# LCD.net
KiCad netlist of a schematic drawn in Altium Designer
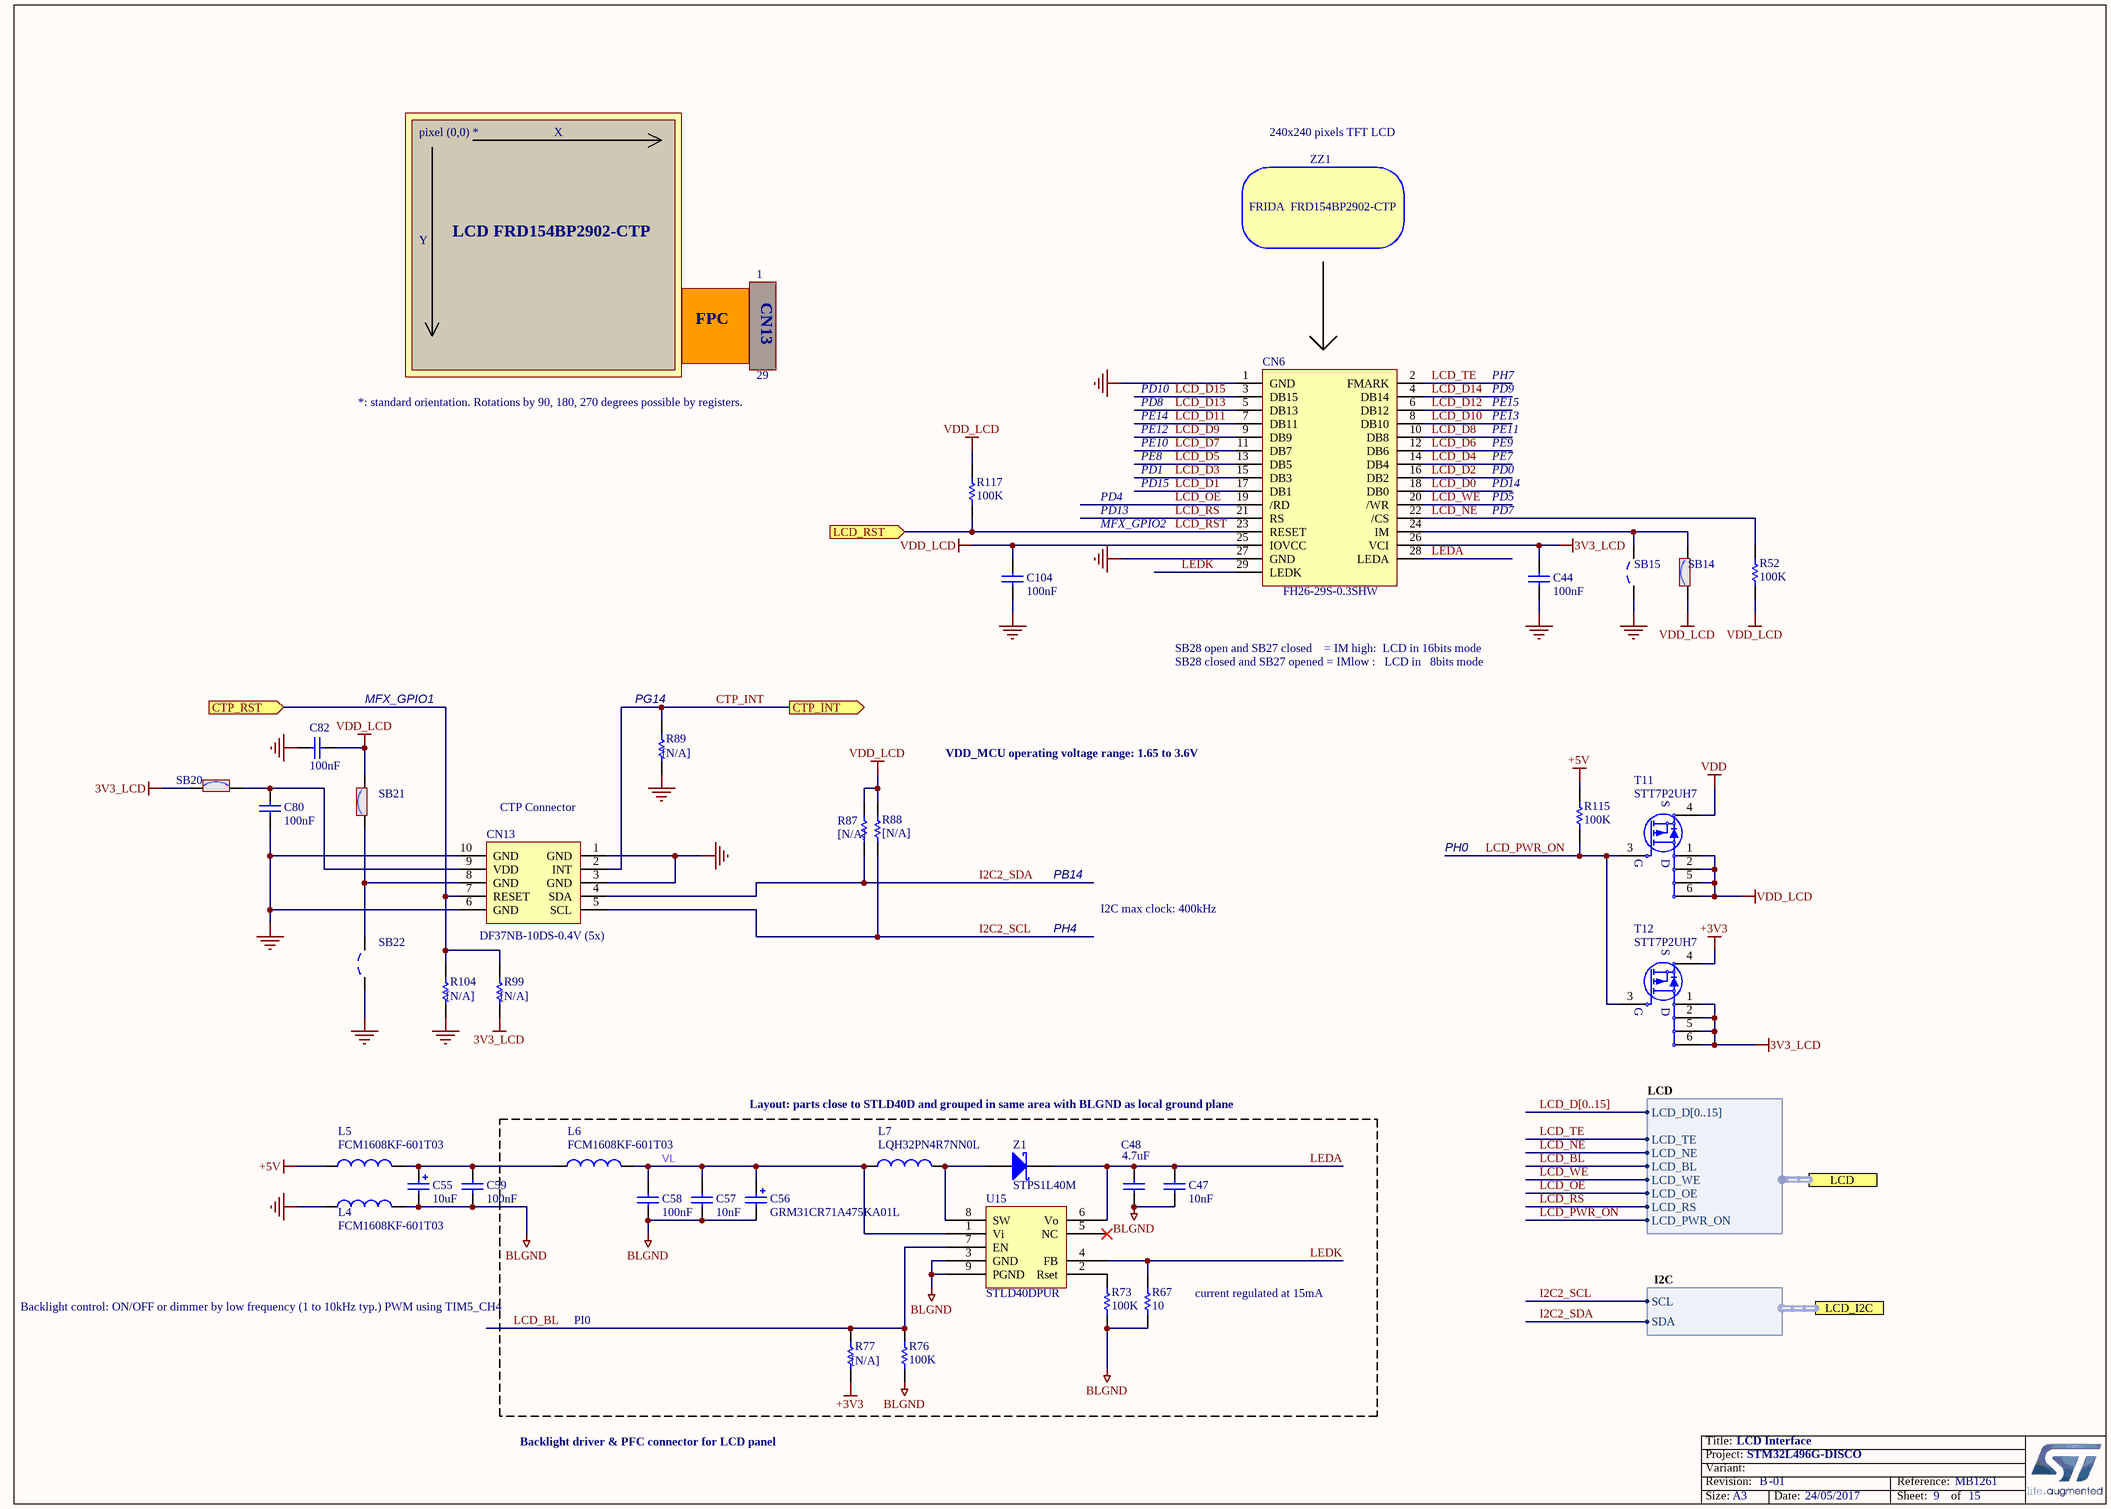
[diagram p0: LCD.SchDoc]

(export (version "E")
  (design (tool "Eeschema 10.0.6"))
  (components
    (comp (ref "C44")
      (value "100nF")
      (footprint "0603C")
      (description "Capacitor,100nF,10%,16V,X7R,0603,YAGEO")
      (fields (field (name "Comment") "CC0603KRX7R7BB104") (field (name "PUBLISHER") "Altium Limited"))
      (libsource (lib "Miscellaneous Devices") (part "Cap"))
    )
    (comp (ref "C47")
      (value "10nF")
      (footprint "0603C")
      (description "Capacitor,10nF,0603,50V,10%,X7R,YAGEO;")
      (fields (field (name "Comment") "CC0603KRX7R9BB103") (field (name "PUBLISHER") "Altium Limited"))
      (libsource (lib "Miscellaneous Devices") (part "Cap"))
    )
    (comp (ref "C48")
      (value "4.7uF")
      (footprint "1206C")
      (description "Capacitor,4.7uF,50V,X7R,10%,1206")
      (fields (field (name "Comment") "CC1206KKX7R9BB475") (field (name "PUBLISHER") "Altium Limited"))
      (libsource (lib "Miscellaneous Devices") (part "CAP"))
    )
    (comp (ref "C55")
      (value "10uF")
      (footprint "TAN-A")
      (description "TAN Capacitor,10uF,10%,16V,A Type,AVX")
      (fields (field (name "Comment") "TAJA106K016R") (field (name "PUBLISHER") "Altium Limited"))
      (libsource (lib "Miscellaneous Devices") (part "Cap Pol1"))
    )
    (comp (ref "C56")
      (value "GRM31CR71A475KA01L")
      (footprint "1206C")
      (description "Capacitor,4.7uF,±10%,X7R,10V,1206,GRM31CR71A475KA01L")
      (fields (field (name "PUBLISHER") "Altium Limited"))
      (libsource (lib "Miscellaneous Devices") (part "Cap Pol1"))
    )
    (comp (ref "C57")
      (value "10nF")
      (footprint "0603C")
      (description "Capacitor,10nF,0603,50V,10%,X7R,YAGEO;")
      (fields (field (name "Comment") "CC0603KRX7R9BB103") (field (name "PUBLISHER") "Altium Limited"))
      (libsource (lib "Miscellaneous Devices") (part "Cap"))
    )
    (comp (ref "C58")
      (value "100nF")
      (footprint "0603C")
      (description "Capacitor,100nF,10%,16V,X7R,0603,YAGEO")
      (fields (field (name "Comment") "CC0603KRX7R7BB104") (field (name "PUBLISHER") "Altium Limited"))
      (libsource (lib "Miscellaneous Devices") (part "Cap"))
    )
    (comp (ref "C59")
      (value "100nF")
      (footprint "0603C")
      (description "Capacitor,100nF,10%,16V,X7R,0603,YAGEO")
      (fields (field (name "Comment") "CC0603KRX7R7BB104") (field (name "PUBLISHER") "Altium Limited"))
      (libsource (lib "Miscellaneous Devices") (part "Cap"))
    )
    (comp (ref "C80")
      (value "100nF")
      (footprint "0603C")
      (description "Capacitor,100nF,10%,16V,X7R,0603,YAGEO")
      (fields (field (name "Comment") "CC0603KRX7R7BB104") (field (name "PUBLISHER") "Altium Limited"))
      (libsource (lib "Miscellaneous Devices") (part "Cap"))
    )
    (comp (ref "C82")
      (value "100nF")
      (footprint "0603C")
      (description "Capacitor,100nF,10%,16V,X7R,0603,YAGEO")
      (fields (field (name "Comment") "CC0603KRX7R7BB104") (field (name "PUBLISHER") "Altium Limited"))
      (libsource (lib "Miscellaneous Devices") (part "Cap"))
    )
    (comp (ref "C104")
      (value "100nF")
      (footprint "0603C")
      (description "Capacitor,100nF,10%,16V,X7R,0603,YAGEO")
      (fields (field (name "Comment") "CC0603KRX7R7BB104") (field (name "PUBLISHER") "Altium Limited"))
      (libsource (lib "Miscellaneous Devices") (part "Cap"))
    )
    (comp (ref "CN6")
      (value "FH26-29S-0.3SHW")
      (footprint "FH26-29S-0R3SHW")
      (description "29pins FPC connector")
      (libsource (lib "MB1209_3") (part "FH26-29S-0.3SHW"))
    )
    (comp (ref "CN13")
      (value "DF37NB-10DS-0.4V (5x)")
      (footprint "DF37NB-10DS-0R4V")
      (description "Header, 5-Pin, Dual row")
      (fields (field (name "PUBLISHER") "Altium Limited"))
      (libsource (lib "MB1209") (part "Header 5X2A"))
    )
    (comp (ref "L4")
      (value "FCM1608KF-601T03")
      (footprint "0603L")
      (description "100uH Bead")
      (fields (field (name "PUBLISHER") "Altium Limited"))
      (libsource (lib "Miscellaneous Devices") (part "Inductor"))
    )
    (comp (ref "L5")
      (value "FCM1608KF-601T03")
      (footprint "0603L")
      (description "100uH Bead")
      (fields (field (name "PUBLISHER") "Altium Limited"))
      (libsource (lib "Miscellaneous Devices") (part "Inductor"))
    )
    (comp (ref "L6")
      (value "FCM1608KF-601T03")
      (footprint "0603L")
      (description "100uH Bead")
      (fields (field (name "PUBLISHER") "Altium Limited"))
      (libsource (lib "Miscellaneous Devices") (part "Inductor"))
    )
    (comp (ref "L7")
      (value "LQH32PN4R7NN0L")
      (footprint "1210L")
      (description "IND,4.7uH,1A,1210,LQH32PN4R7NN0L")
      (fields (field (name "PUBLISHER") "Altium Limited"))
      (libsource (lib "Miscellaneous Devices") (part "Inductor"))
    )
    (comp (ref "R52")
      (value "100K")
      (footprint "0603R")
      (description "Resistor,100K,0603,1%,YAGEO")
      (fields (field (name "Comment") "RC0603FR-07100KL") (field (name "PUBLISHER") "Altium Limited"))
      (libsource (lib "Miscellaneous Devices") (part "res1"))
    )
    (comp (ref "R67")
      (value "10")
      (footprint "0603R")
      (description "Resistor,10R,0603,1%,YAGEO")
      (fields (field (name "Comment") "RC0603FR-0710RL") (field (name "PUBLISHER") "Altium Limited"))
      (libsource (lib "Miscellaneous Devices") (part "res1"))
    )
    (comp (ref "R73")
      (value "100K")
      (footprint "0603R")
      (description "Resistor,100K,0603,1%,YAGEO")
      (fields (field (name "Comment") "RC0603FR-07100KL") (field (name "PUBLISHER") "Altium Limited"))
      (libsource (lib "Miscellaneous Devices") (part "res1"))
    )
    (comp (ref "R76")
      (value "100K")
      (footprint "0603R")
      (description "Resistor,100K,0603,1%,YAGEO")
      (fields (field (name "Comment") "RC0603FR-07100KL") (field (name "PUBLISHER") "Altium Limited"))
      (libsource (lib "Miscellaneous Devices") (part "res1"))
    )
    (comp (ref "R77")
      (value "[N/A]")
      (footprint "0603R")
      (description "Resistor,100K,0603,1%,YAGEO")
      (fields (field (name "PUBLISHER") "Altium Limited"))
      (libsource (lib "Miscellaneous Devices") (part "res1"))
    )
    (comp (ref "R87")
      (value "[N/A]")
      (footprint "0603R")
      (description "Resistor,1.5K,0603,1%,YAGEO")
      (fields (field (name "PUBLISHER") "Altium Limited"))
      (libsource (lib "Miscellaneous Devices") (part "res1"))
    )
    (comp (ref "R88")
      (value "[N/A]")
      (footprint "0603R")
      (description "Resistor,1.5K,0603,1%,YAGEO")
      (fields (field (name "PUBLISHER") "Altium Limited"))
      (libsource (lib "Miscellaneous Devices") (part "res1"))
    )
    (comp (ref "R89")
      (value "[N/A]")
      (footprint "0603R")
      (description "Resistor,100K,0603,1%,YAGEO")
      (fields (field (name "PUBLISHER") "Altium Limited"))
      (libsource (lib "Miscellaneous Devices") (part "res1"))
    )
    (comp (ref "R99")
      (value "[N/A]")
      (footprint "0603R")
      (description "Resistor,100K,0603,1%,YAGEO")
      (fields (field (name "PUBLISHER") "Altium Limited"))
      (libsource (lib "Miscellaneous Devices") (part "res1"))
    )
    (comp (ref "R104")
      (value "[N/A]")
      (footprint "0603R")
      (description "Resistor,100K,0603,1%,YAGEO")
      (fields (field (name "PUBLISHER") "Altium Limited"))
      (libsource (lib "Miscellaneous Devices") (part "res1"))
    )
    (comp (ref "R115")
      (value "100K")
      (footprint "0603R")
      (description "Resistor,100K,0603,1%,YAGEO")
      (fields (field (name "Comment") "RC0603FR-07100KL") (field (name "PUBLISHER") "Altium Limited"))
      (libsource (lib "Miscellaneous Devices") (part "res1"))
    )
    (comp (ref "R117")
      (value "100K")
      (footprint "0603R")
      (description "Resistor,100K,0603,1%,YAGEO")
      (fields (field (name "Comment") "RC0603FR-07100KL") (field (name "PUBLISHER") "Altium Limited"))
      (libsource (lib "Miscellaneous Devices") (part "res1"))
    )
    (comp (ref "SB14")
      (value "Solder Bridge ON")
      (footprint "SB_0603")
      (libsource (lib "MCD_TOOLS") (part "SB_ON"))
    )
    (comp (ref "SB15")
      (value "Solder Bridge OFF")
      (footprint "SB_0603")
      (libsource (lib "MCD_TOOLS") (part "SB_OFF"))
    )
    (comp (ref "SB20") (value "Solder Bridge ON") (footprint "SB_0603") (libsource (lib "") (part "SB_ON_1")))
    (comp (ref "SB21")
      (value "Solder Bridge ON")
      (footprint "SB_0603")
      (libsource (lib "MCD_TOOLS") (part "SB_ON"))
    )
    (comp (ref "SB22")
      (value "Solder Bridge OFF")
      (footprint "SB_0603")
      (libsource (lib "MCD_TOOLS") (part "SB_OFF"))
    )
    (comp (ref "T11")
      (value "STT7P2UH7")
      (footprint "SOT23-6L")
      (description "STripFET VII DeepGATE Power MOSFET, P-CHANNEL 20 V, 0.0146, 7 A - SOT23-6L")
      (libsource (lib "MCD_TOOLS") (part "STT7P2UH7"))
    )
    (comp (ref "T12")
      (value "STT7P2UH7")
      (footprint "SOT23-6L")
      (description "STripFET VII DeepGATE Power MOSFET, P-CHANNEL 20 V, 0.0146, 7 A - SOT23-6L")
      (libsource (lib "MCD_TOOLS") (part "STT7P2UH7"))
    )
    (comp (ref "U15")
      (value "STLD40DPUR")
      (footprint "SON8_0R65_3X3")
      (libsource (lib "3.2LCD_daughterboard") (part "STLD40DPMR"))
    )
    (comp (ref "Z1")
      (value "STPS1L40M")
      (footprint "DO-216AA")
      (description "Schottky Diode")
      (fields (field (name "PUBLISHER") "Altium Limited"))
      (libsource (lib "Miscellaneous Devices") (part "D Schottky"))
    )
    (comp (ref "ZZ1")
      (value "FRIDA  FRD154BP2902-CTP")
      (footprint "LCD_FRD154BP2902-CTP")
      (libsource (lib "Almos") (part "BoM_Item"))
    )
  )
  (nets
    (net (code "3") (name "+3V3") (class "Default")
      (node (ref "R77") (pin "2") (pinfunction "2_2") (pintype "passive"))
      (node (ref "T12") (pin "4") (pinfunction "S_4") (pintype "passive"))
    )
    (net (code "4") (name "+5V") (class "Default")
      (node (ref "L5") (pin "1") (pinfunction "1_1") (pintype "passive"))
      (node (ref "R115") (pin "1") (pinfunction "1_1") (pintype "passive"))
    )
    (net (code "5") (name "/CTP_INT") (class "Default")
      (node (ref "CN13") (pin "2") (pinfunction "INT_2") (pintype "passive"))
      (node (ref "R89") (pin "1") (pinfunction "1_1") (pintype "passive"))
    )
    (net (code "6") (name "/CTP_RST") (class "Default")
      (node (ref "CN13") (pin "7") (pinfunction "RESET_7") (pintype "passive"))
      (node (ref "R104") (pin "1") (pinfunction "1_1") (pintype "passive"))
      (node (ref "R99") (pin "1") (pinfunction "1_1") (pintype "passive"))
    )
    (net (code "7") (name "/I2C2_SCL") (class "Default")
      (node (ref "CN13") (pin "5") (pinfunction "SCL_5") (pintype "passive"))
      (node (ref "R88") (pin "2") (pinfunction "2_2") (pintype "passive"))
    )
    (net (code "8") (name "/I2C2_SDA") (class "Default")
      (node (ref "CN13") (pin "4") (pinfunction "SDA_4") (pintype "passive"))
      (node (ref "R87") (pin "1") (pinfunction "1_1") (pintype "passive"))
    )
    (net (code "9") (name "/LCD_BL") (class "Default")
      (node (ref "R76") (pin "1") (pinfunction "1_1") (pintype "passive"))
      (node (ref "R77") (pin "1") (pinfunction "1_1") (pintype "passive"))
      (node (ref "U15") (pin "7") (pinfunction "EN_7") (pintype "passive"))
    )
    (net (code "10") (name "/LCD_D0") (class "Default")
      (node (ref "CN6") (pin "18") (pinfunction "DB0_18") (pintype "passive"))
    )
    (net (code "11") (name "/LCD_D1") (class "Default")
      (node (ref "CN6") (pin "17") (pinfunction "DB1_17") (pintype "passive"))
    )
    (net (code "12") (name "/LCD_D2") (class "Default")
      (node (ref "CN6") (pin "16") (pinfunction "DB2_16") (pintype "passive"))
    )
    (net (code "13") (name "/LCD_D3") (class "Default")
      (node (ref "CN6") (pin "15") (pinfunction "DB3_15") (pintype "passive"))
    )
    (net (code "14") (name "/LCD_D4") (class "Default")
      (node (ref "CN6") (pin "14") (pinfunction "DB4_14") (pintype "passive"))
    )
    (net (code "15") (name "/LCD_D5") (class "Default")
      (node (ref "CN6") (pin "13") (pinfunction "DB5_13") (pintype "passive"))
    )
    (net (code "16") (name "/LCD_D6") (class "Default")
      (node (ref "CN6") (pin "12") (pinfunction "DB6_12") (pintype "passive"))
    )
    (net (code "17") (name "/LCD_D7") (class "Default")
      (node (ref "CN6") (pin "11") (pinfunction "DB7_11") (pintype "passive"))
    )
    (net (code "18") (name "/LCD_D8") (class "Default")
      (node (ref "CN6") (pin "10") (pinfunction "DB8_10") (pintype "passive"))
    )
    (net (code "19") (name "/LCD_D9") (class "Default")
      (node (ref "CN6") (pin "9") (pinfunction "DB9_9") (pintype "passive"))
    )
    (net (code "20") (name "/LCD_D10") (class "Default")
      (node (ref "CN6") (pin "8") (pinfunction "DB10_8") (pintype "passive"))
    )
    (net (code "21") (name "/LCD_D11") (class "Default")
      (node (ref "CN6") (pin "7") (pinfunction "DB11_7") (pintype "passive"))
    )
    (net (code "22") (name "/LCD_D12") (class "Default")
      (node (ref "CN6") (pin "6") (pinfunction "DB12_6") (pintype "passive"))
    )
    (net (code "23") (name "/LCD_D13") (class "Default")
      (node (ref "CN6") (pin "5") (pinfunction "DB13_5") (pintype "passive"))
    )
    (net (code "24") (name "/LCD_D14") (class "Default")
      (node (ref "CN6") (pin "4") (pinfunction "DB14_4") (pintype "passive"))
    )
    (net (code "25") (name "/LCD_D15") (class "Default")
      (node (ref "CN6") (pin "3") (pinfunction "DB15_3") (pintype "passive"))
    )
    (net (code "27") (name "/LCD_NE") (class "Default")
      (node (ref "CN6") (pin "22") (pinfunction "/CS_22") (pintype "passive"))
      (node (ref "R52") (pin "1") (pinfunction "1_1") (pintype "passive"))
    )
    (net (code "28") (name "/LCD_OE") (class "Default")
      (node (ref "CN6") (pin "19") (pinfunction "/RD_19") (pintype "passive"))
    )
    (net (code "29") (name "/LCD_PWR_ON") (class "Default")
      (node (ref "R115") (pin "2") (pinfunction "2_2") (pintype "passive"))
      (node (ref "T11") (pin "3") (pinfunction "G_3") (pintype "passive"))
      (node (ref "T12") (pin "3") (pinfunction "G_3") (pintype "passive"))
    )
    (net (code "30") (name "/LCD_RS") (class "Default")
      (node (ref "CN6") (pin "21") (pinfunction "RS_21") (pintype "passive"))
    )
    (net (code "31") (name "/LCD_RST") (class "Default")
      (node (ref "CN6") (pin "23") (pinfunction "RESET_23") (pintype "passive"))
      (node (ref "R117") (pin "2") (pinfunction "2_2") (pintype "passive"))
    )
    (net (code "32") (name "/LCD_TE") (class "Default")
      (node (ref "CN6") (pin "2") (pinfunction "FMARK_2") (pintype "passive"))
    )
    (net (code "33") (name "/LCD_WE") (class "Default")
      (node (ref "CN6") (pin "20") (pinfunction "/WR_20") (pintype "passive"))
    )
    (net (code "34") (name "/LEDA") (class "Default")
      (node (ref "C47") (pin "1") (pinfunction "1_1") (pintype "passive"))
      (node (ref "C48") (pin "1") (pinfunction "1_1") (pintype "passive"))
      (node (ref "CN6") (pin "28") (pinfunction "LEDA_28") (pintype "passive"))
      (node (ref "U15") (pin "6") (pinfunction "Vo_6") (pintype "passive"))
      (node (ref "Z1") (pin "2") (pinfunction "K_2") (pintype "passive"))
    )
    (net (code "35") (name "/LEDK") (class "Default")
      (node (ref "CN6") (pin "29") (pinfunction "LEDK_29") (pintype "passive"))
      (node (ref "R67") (pin "1") (pinfunction "1_1") (pintype "passive"))
      (node (ref "U15") (pin "4") (pinfunction "FB_4") (pintype "passive"))
    )
    (net (code "36") (name "/VL") (class "Default")
      (node (ref "C56") (pin "1") (pinfunction "1_1") (pintype "passive"))
      (node (ref "C57") (pin "1") (pinfunction "1_1") (pintype "passive"))
      (node (ref "C58") (pin "1") (pinfunction "1_1") (pintype "passive"))
      (node (ref "L6") (pin "2") (pinfunction "2_2") (pintype "passive"))
      (node (ref "L7") (pin "1") (pinfunction "1_1") (pintype "passive"))
      (node (ref "U15") (pin "1") (pinfunction "Vi_1") (pintype "passive"))
    )
    (net (code "39") (name "3V3_LCD") (class "Default")
      (node (ref "C44") (pin "1") (pinfunction "1_1") (pintype "passive"))
      (node (ref "CN6") (pin "26") (pinfunction "VCI_26") (pintype "passive"))
      (node (ref "R99") (pin "2") (pinfunction "2_2") (pintype "passive"))
      (node (ref "SB20") (pin "1") (pinfunction "1_1") (pintype "passive"))
      (node (ref "T12") (pin "1") (pinfunction "S_1") (pintype "passive"))
      (node (ref "T12") (pin "2") (pinfunction "S_2") (pintype "passive"))
      (node (ref "T12") (pin "5") (pinfunction "D_5") (pintype "passive"))
      (node (ref "T12") (pin "6") (pinfunction "D_6") (pintype "passive"))
    )
    (net (code "40") (name "BLGND") (class "Default")
      (node (ref "C47") (pin "2") (pinfunction "2_2") (pintype "passive"))
      (node (ref "C48") (pin "2") (pinfunction "2_2") (pintype "passive"))
      (node (ref "C55") (pin "2") (pinfunction "2_2") (pintype "passive"))
      (node (ref "C56") (pin "2") (pinfunction "2_2") (pintype "passive"))
      (node (ref "C57") (pin "2") (pinfunction "2_2") (pintype "passive"))
      (node (ref "C58") (pin "2") (pinfunction "2_2") (pintype "passive"))
      (node (ref "C59") (pin "2") (pinfunction "2_2") (pintype "passive"))
      (node (ref "L4") (pin "2") (pinfunction "2_2") (pintype "passive"))
      (node (ref "R67") (pin "2") (pinfunction "2_2") (pintype "passive"))
      (node (ref "R73") (pin "2") (pinfunction "2_2") (pintype "passive"))
      (node (ref "R76") (pin "2") (pinfunction "2_2") (pintype "passive"))
      (node (ref "U15") (pin "3") (pinfunction "GND_3") (pintype "passive"))
      (node (ref "U15") (pin "9") (pinfunction "PGND_9") (pintype "passive"))
    )
    (net (code "41") (name "GND") (class "Default")
      (node (ref "C104") (pin "2") (pinfunction "2_2") (pintype "passive"))
      (node (ref "C44") (pin "2") (pinfunction "2_2") (pintype "passive"))
      (node (ref "C80") (pin "2") (pinfunction "2_2") (pintype "passive"))
      (node (ref "C82") (pin "2") (pinfunction "2_2") (pintype "passive"))
      (node (ref "CN13") (pin "1") (pinfunction "GND_1") (pintype "passive"))
      (node (ref "CN13") (pin "10") (pinfunction "GND_10") (pintype "passive"))
      (node (ref "CN13") (pin "3") (pinfunction "GND_3") (pintype "passive"))
      (node (ref "CN13") (pin "6") (pinfunction "GND_6") (pintype "passive"))
      (node (ref "CN6") (pin "1") (pinfunction "GND_1") (pintype "passive"))
      (node (ref "CN6") (pin "27") (pinfunction "GND_27") (pintype "passive"))
      (node (ref "L4") (pin "1") (pinfunction "1_1") (pintype "passive"))
      (node (ref "R104") (pin "2") (pinfunction "2_2") (pintype "passive"))
      (node (ref "R89") (pin "2") (pinfunction "2_2") (pintype "passive"))
      (node (ref "SB15") (pin "1") (pinfunction "1_1") (pintype "passive"))
      (node (ref "SB22") (pin "1") (pinfunction "1_1") (pintype "passive"))
    )
    (net (code "42") (name "Net-(C55-Pad1)") (class "Default")
      (node (ref "C55") (pin "1") (pinfunction "1_1") (pintype "passive"))
      (node (ref "C59") (pin "1") (pinfunction "1_1") (pintype "passive"))
      (node (ref "L5") (pin "2") (pinfunction "2_2") (pintype "passive"))
      (node (ref "L6") (pin "1") (pinfunction "1_1") (pintype "passive"))
    )
    (net (code "43") (name "Net-(CN6-IM)") (class "Default")
      (node (ref "CN6") (pin "24") (pinfunction "IM_24") (pintype "passive"))
      (node (ref "SB14") (pin "2") (pinfunction "2_2") (pintype "passive"))
      (node (ref "SB15") (pin "2") (pinfunction "2_2") (pintype "passive"))
    )
    (net (code "44") (name "Net-(CN13-GND-Pad8)") (class "Default")
      (node (ref "CN13") (pin "8") (pinfunction "GND_8") (pintype "passive"))
      (node (ref "SB21") (pin "1") (pinfunction "1_1") (pintype "passive"))
      (node (ref "SB22") (pin "2") (pinfunction "2_2") (pintype "passive"))
    )
    (net (code "45") (name "Net-(CN13-VDD)") (class "Default")
      (node (ref "C80") (pin "1") (pinfunction "1_1") (pintype "passive"))
      (node (ref "CN13") (pin "9") (pinfunction "VDD_9") (pintype "passive"))
      (node (ref "SB20") (pin "2") (pinfunction "2_2") (pintype "passive"))
    )
    (net (code "46") (name "Net-(U15-Rset)") (class "Default")
      (node (ref "R73") (pin "1") (pinfunction "1_1") (pintype "passive"))
      (node (ref "U15") (pin "2") (pinfunction "Rset_2") (pintype "passive"))
    )
    (net (code "47") (name "Net-(U15-SW)") (class "Default")
      (node (ref "L7") (pin "2") (pinfunction "2_2") (pintype "passive"))
      (node (ref "U15") (pin "8") (pinfunction "SW_8") (pintype "passive"))
      (node (ref "Z1") (pin "1") (pinfunction "A_1") (pintype "passive"))
    )
    (net (code "48") (name "VDD") (class "Default")
      (node (ref "T11") (pin "4") (pinfunction "S_4") (pintype "passive"))
    )
    (net (code "49") (name "VDD_LCD") (class "Default")
      (node (ref "C104") (pin "1") (pinfunction "1_1") (pintype "passive"))
      (node (ref "C82") (pin "1") (pinfunction "1_1") (pintype "passive"))
      (node (ref "CN6") (pin "25") (pinfunction "IOVCC_25") (pintype "passive"))
      (node (ref "R117") (pin "1") (pinfunction "1_1") (pintype "passive"))
      (node (ref "R52") (pin "2") (pinfunction "2_2") (pintype "passive"))
      (node (ref "R87") (pin "2") (pinfunction "2_2") (pintype "passive"))
      (node (ref "R88") (pin "1") (pinfunction "1_1") (pintype "passive"))
      (node (ref "SB14") (pin "1") (pinfunction "1_1") (pintype "passive"))
      (node (ref "SB21") (pin "2") (pinfunction "2_2") (pintype "passive"))
      (node (ref "T11") (pin "1") (pinfunction "S_1") (pintype "passive"))
      (node (ref "T11") (pin "2") (pinfunction "S_2") (pintype "passive"))
      (node (ref "T11") (pin "5") (pinfunction "D_5") (pintype "passive"))
      (node (ref "T11") (pin "6") (pinfunction "D_6") (pintype "passive"))
    )
    (net (code "50") (name "unconnected-(U15-NC-Pad5)") (class "Default")
      (node (ref "U15") (pin "5") (pinfunction "NC_5") (pintype "passive+no_connect"))
    )
  )
)
